# ESP32_2.net
KiCad netlist of a schematic drawn in EAGLE
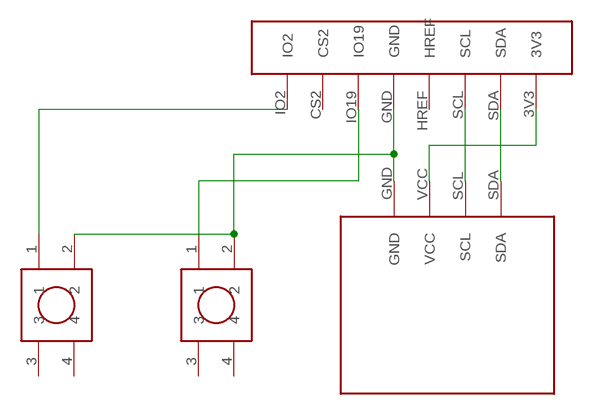
[diagram p0: schematic, sheet 1]

(export (version "E")
  (design (tool "Eeschema 10.0.6"))
  (components
    (comp (ref "U$1")
      (value "TACT_BUTTON")
      (footprint "eagle-import:TACT_BUTTON")
      (libsource (lib "eagle-import") (part "TACT_BUTTON"))
    )
    (comp (ref "U$2")
      (value "TACT_BUTTON")
      (footprint "eagle-import:TACT_BUTTON")
      (libsource (lib "eagle-import") (part "TACT_BUTTON"))
    )
    (comp (ref "U$3")
      (value "OLED_0.96\"")
      (footprint "eagle-import:OLED_0.96_")
      (libsource (lib "eagle-import") (part "OLED_0.96{dblquote}"))
    )
    (comp (ref "U$4")
      (value "ESP32_1X8")
      (footprint "eagle-import:ESP32_1X8")
      (libsource (lib "eagle-import") (part "ESP32_1X8"))
    )
  )
  (nets
    (net (code "1") (name "Net-(U$1-Pad1)") (class "Default")
      (node (ref "U$1") (pin "1") (pinfunction "1_1") (pintype "bidirectional"))
      (node (ref "U$4") (pin "IO2") (pinfunction "IO2_IO2") (pintype "bidirectional"))
    )
    (net (code "2") (name "Net-(U$1-Pad2)") (class "Default")
      (node (ref "U$1") (pin "2") (pinfunction "2_2") (pintype "bidirectional"))
      (node (ref "U$2") (pin "2") (pinfunction "2_2") (pintype "bidirectional"))
      (node (ref "U$3") (pin "GND") (pinfunction "GND_GND") (pintype "bidirectional"))
      (node (ref "U$4") (pin "GND") (pinfunction "GND_GND") (pintype "bidirectional"))
    )
    (net (code "3") (name "Net-(U$2-Pad1)") (class "Default")
      (node (ref "U$2") (pin "1") (pinfunction "1_1") (pintype "bidirectional"))
      (node (ref "U$4") (pin "IO19") (pinfunction "IO19_IO19") (pintype "bidirectional"))
    )
    (net (code "4") (name "Net-(U$3-PadSCL)") (class "Default")
      (node (ref "U$3") (pin "SCL") (pinfunction "SCL_SCL") (pintype "bidirectional"))
      (node (ref "U$4") (pin "SCL") (pinfunction "SCL_SCL") (pintype "bidirectional"))
    )
    (net (code "5") (name "Net-(U$3-PadSDA)") (class "Default")
      (node (ref "U$3") (pin "SDA") (pinfunction "SDA_SDA") (pintype "bidirectional"))
      (node (ref "U$4") (pin "SDA") (pinfunction "SDA_SDA") (pintype "bidirectional"))
    )
    (net (code "6") (name "Net-(U$3-PadVCC)") (class "Default")
      (node (ref "U$3") (pin "VCC") (pinfunction "VCC_VCC") (pintype "bidirectional"))
      (node (ref "U$4") (pin "3V3") (pinfunction "3V3_3V3") (pintype "bidirectional"))
    )
    (net (code "7") (name "unconnected-(U$1-Pad3)") (class "Default")
      (node (ref "U$1") (pin "3") (pinfunction "3_3") (pintype "bidirectional"))
    )
    (net (code "8") (name "unconnected-(U$1-Pad4)") (class "Default")
      (node (ref "U$1") (pin "4") (pinfunction "4_4") (pintype "bidirectional"))
    )
    (net (code "9") (name "unconnected-(U$2-Pad3)") (class "Default")
      (node (ref "U$2") (pin "3") (pinfunction "3_3") (pintype "bidirectional"))
    )
    (net (code "10") (name "unconnected-(U$2-Pad4)") (class "Default")
      (node (ref "U$2") (pin "4") (pinfunction "4_4") (pintype "bidirectional"))
    )
    (net (code "11") (name "unconnected-(U$4-PadCS2)") (class "Default")
      (node (ref "U$4") (pin "CS2") (pinfunction "CS2_CS2") (pintype "bidirectional"))
    )
    (net (code "12") (name "unconnected-(U$4-PadHREF)") (class "Default")
      (node (ref "U$4") (pin "HREF") (pinfunction "HREF_HREF") (pintype "bidirectional"))
    )
  )
)
